# Main_ASCII.net
KiCad netlist of a schematic drawn in Altium Designer
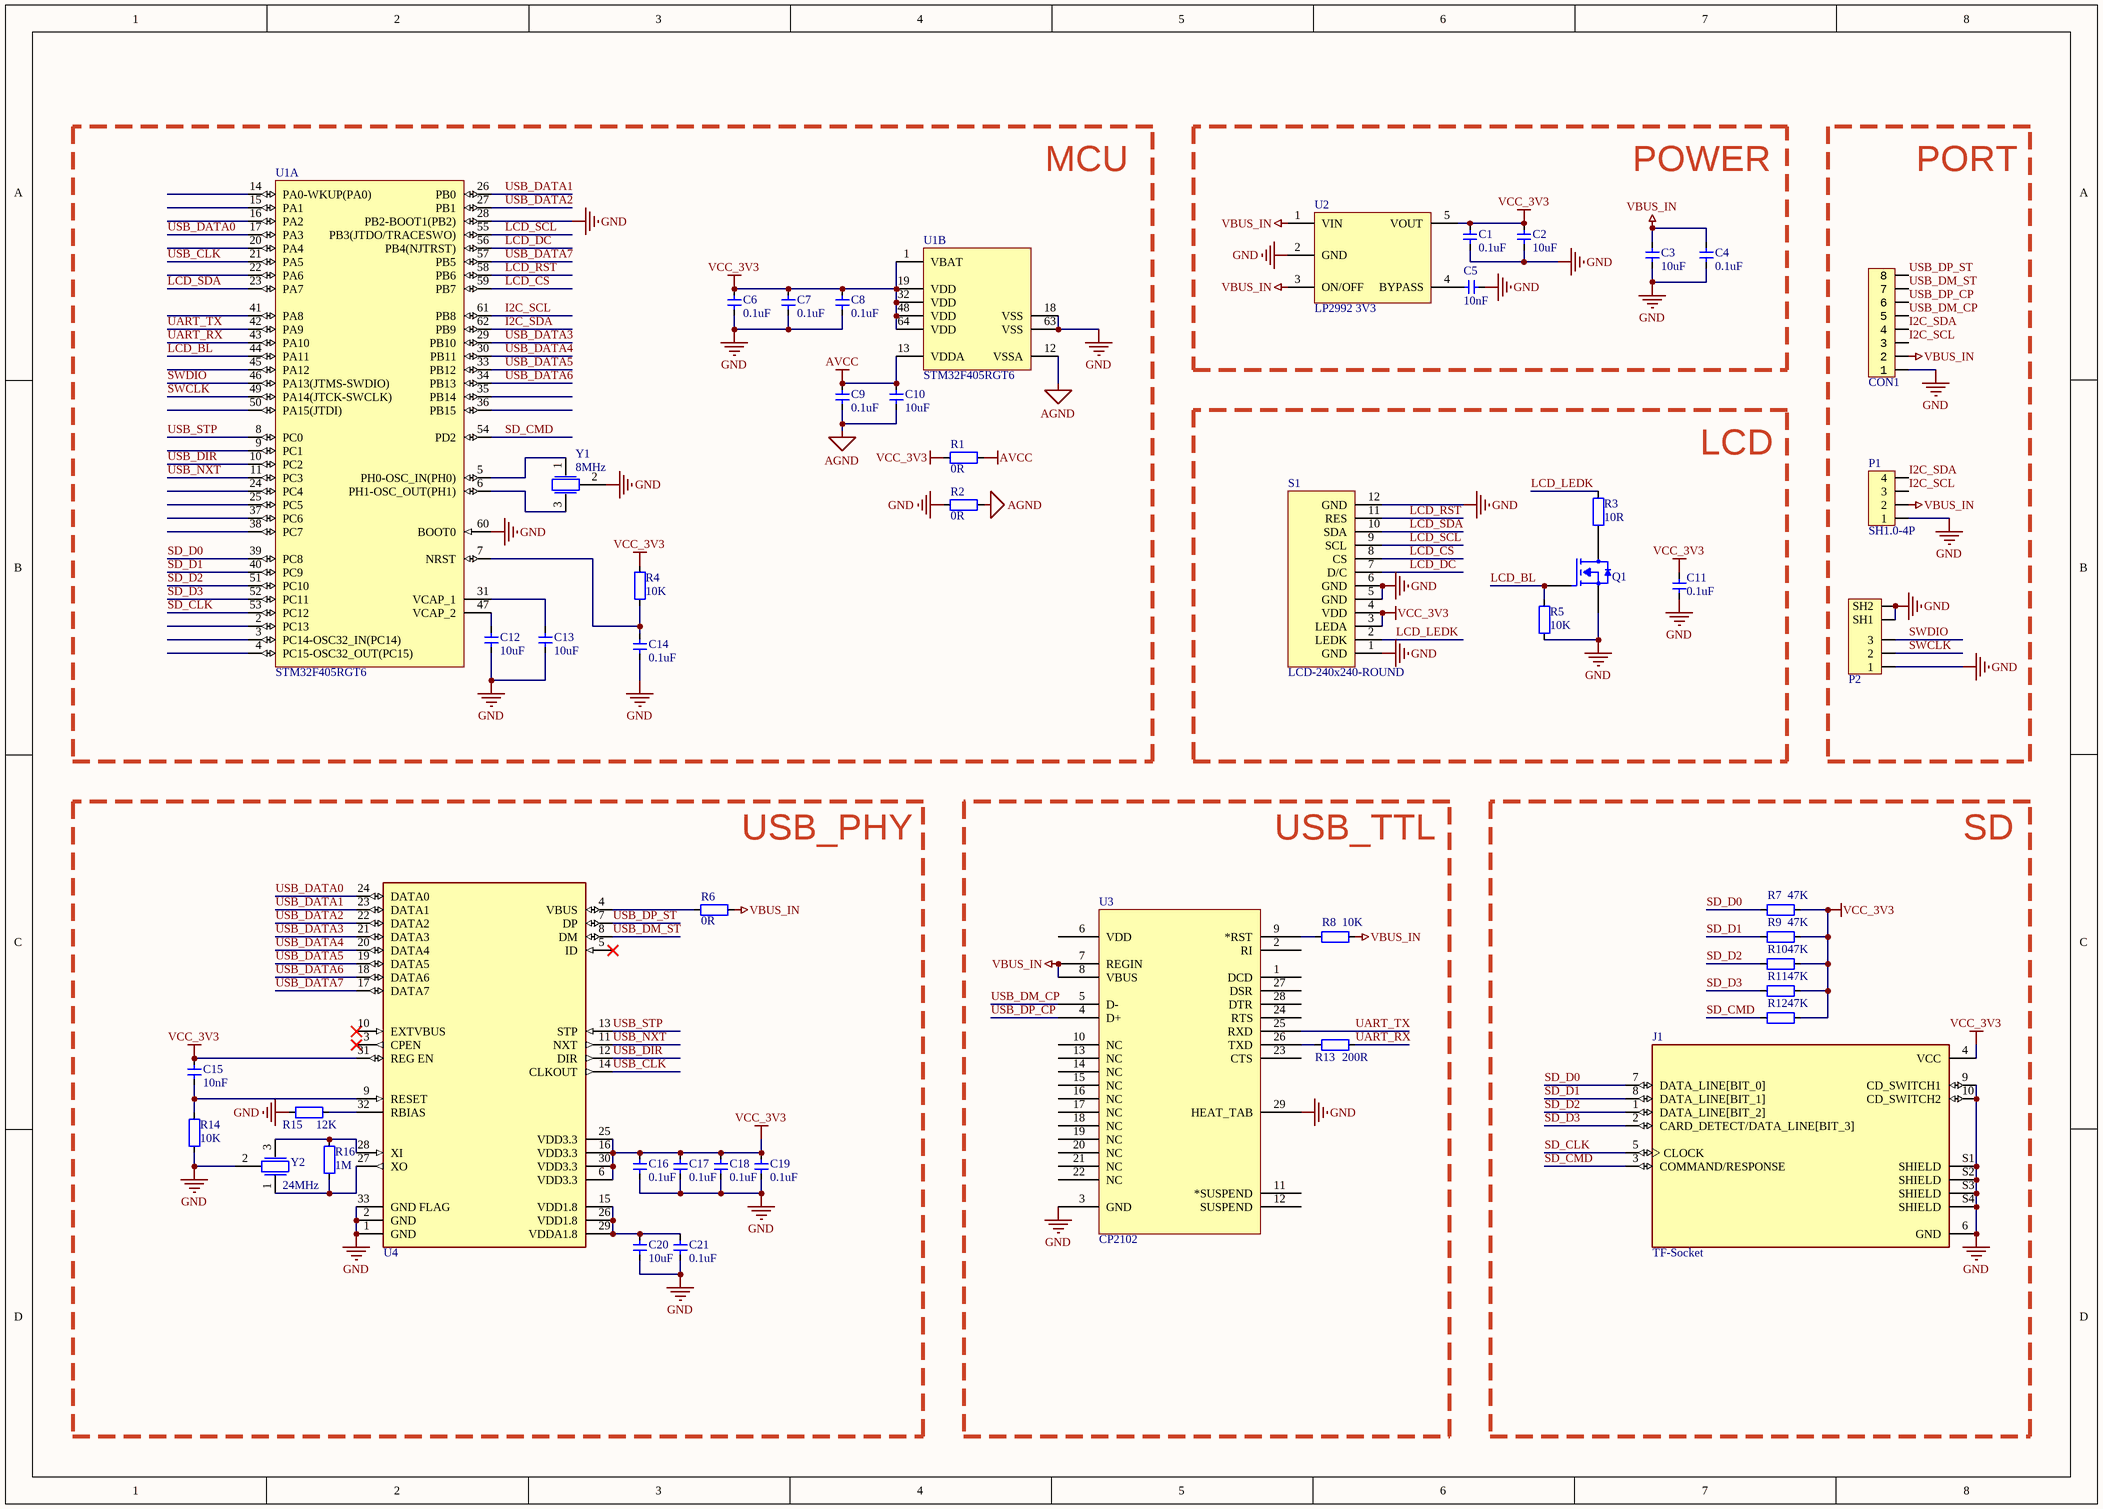
[diagram p0: Main_ASCII.SchDoc]

(export (version "E")
  (design (tool "Eeschema 10.0.6"))
  (components
    (comp (ref "C1")
      (value "0.1uF")
      (footprint "CAP_0402")
      (description "Capacitor")
      (libsource (lib "MyPcbLib") (part "电容-0402"))
    )
    (comp (ref "C2")
      (value "10uF")
      (footprint "CAP_0402")
      (description "Capacitor")
      (libsource (lib "MyPcbLib") (part "电容-0402"))
    )
    (comp (ref "C3")
      (value "10uF")
      (footprint "CAP_0402")
      (description "Capacitor")
      (libsource (lib "MyPcbLib") (part "电容-0402"))
    )
    (comp (ref "C4")
      (value "0.1uF")
      (footprint "CAP_0402")
      (description "Capacitor")
      (libsource (lib "MyPcbLib") (part "电容-0402"))
    )
    (comp (ref "C5")
      (value "10nF")
      (footprint "CAP_0402")
      (description "Capacitor")
      (libsource (lib "MyPcbLib") (part "电容-0402"))
    )
    (comp (ref "C6")
      (value "0.1uF")
      (footprint "CAP_0402")
      (description "Capacitor")
      (libsource (lib "MyPcbLib") (part "电容-0402"))
    )
    (comp (ref "C7")
      (value "0.1uF")
      (footprint "CAP_0402")
      (description "Capacitor")
      (libsource (lib "MyPcbLib") (part "电容-0402"))
    )
    (comp (ref "C8")
      (value "0.1uF")
      (footprint "CAP_0402")
      (description "Capacitor")
      (libsource (lib "MyPcbLib") (part "电容-0402"))
    )
    (comp (ref "C9")
      (value "0.1uF")
      (footprint "CAP_0402")
      (description "Capacitor")
      (libsource (lib "MyPcbLib") (part "电容-0402"))
    )
    (comp (ref "C10")
      (value "10uF")
      (footprint "CAP_0402")
      (description "Capacitor")
      (libsource (lib "MyPcbLib") (part "电容-0402"))
    )
    (comp (ref "C11")
      (value "0.1uF")
      (footprint "CAP_0402")
      (description "Capacitor")
      (libsource (lib "MyPcbLib") (part "电容-0402"))
    )
    (comp (ref "C12")
      (value "10uF")
      (footprint "CAP_0402")
      (description "Capacitor")
      (libsource (lib "MyPcbLib") (part "电容-0402"))
    )
    (comp (ref "C13")
      (value "10uF")
      (footprint "CAP_0402")
      (description "Capacitor")
      (libsource (lib "MyPcbLib") (part "电容-0402"))
    )
    (comp (ref "C14")
      (value "0.1uF")
      (footprint "CAP_0402")
      (description "Capacitor")
      (libsource (lib "MyPcbLib") (part "电容-0402"))
    )
    (comp (ref "C15")
      (value "10nF")
      (footprint "CAP_0402")
      (description "Capacitor")
      (libsource (lib "MyPcbLib") (part "电容-0402"))
    )
    (comp (ref "C16")
      (value "0.1uF")
      (footprint "CAP_0402")
      (description "Capacitor")
      (libsource (lib "MyPcbLib") (part "电容-0402"))
    )
    (comp (ref "C17")
      (value "0.1uF")
      (footprint "CAP_0402")
      (description "Capacitor")
      (libsource (lib "MyPcbLib") (part "电容-0402"))
    )
    (comp (ref "C18")
      (value "0.1uF")
      (footprint "CAP_0402")
      (description "Capacitor")
      (libsource (lib "MyPcbLib") (part "电容-0402"))
    )
    (comp (ref "C19")
      (value "0.1uF")
      (footprint "CAP_0402")
      (description "Capacitor")
      (libsource (lib "MyPcbLib") (part "电容-0402"))
    )
    (comp (ref "C20")
      (value "10uF")
      (footprint "CAP_0402")
      (description "Capacitor")
      (libsource (lib "MyPcbLib") (part "电容-0402"))
    )
    (comp (ref "C21")
      (value "0.1uF")
      (footprint "CAP_0402")
      (description "Capacitor")
      (libsource (lib "MyPcbLib") (part "电容-0402"))
    )
    (comp (ref "CON1")
      (value "FFC_0.5_8")
      (footprint "FFC_0.5_8")
      (description "FFC")
      (libsource (lib "KitSprout") (part "FFC_0.5_8"))
    )
    (comp (ref "J1")
      (value "TF-Socket")
      (footprint "TF-Card-Amphenol with TF")
      (description "10 _8 + 2_ Position Card Connector Secure Digital - microSDâ„¢ Surface Mount, Right Angle Gold")
      (fields (field (name "MP") "1140084168") (field (name "MF") "Amphenol Commercial Products"))
      (libsource (lib "MyPcbLib") (part "TF-Socket"))
    )
    (comp (ref "P1") (value "SH1.0-4P") (footprint "SH1.0-4P") (libsource (lib "MyPcbLib") (part "SH1.0-4P")))
    (comp (ref "P2")
      (value "SH1.0-3P-STAND")
      (footprint "SH1.0-3P-STAND")
      (description "Header")
      (libsource (lib "MyPcbLib") (part "SH1.0-3P-STAND"))
    )
    (comp (ref "Q1")
      (value "AO3400A")
      (footprint "SOT23-3")
      (description "N-MOS")
      (libsource (lib "MyPcbLib") (part "AO3400A"))
    )
    (comp (ref "R1")
      (value "0R")
      (footprint "RES_0402")
      (description "Resistor")
      (libsource (lib "") (part "电阻-0402_1"))
    )
    (comp (ref "R2")
      (value "0R")
      (footprint "RES_0402")
      (description "Resistor")
      (libsource (lib "") (part "电阻-0402_1"))
    )
    (comp (ref "R3")
      (value "10R")
      (footprint "RES_0402")
      (description "Resistor")
      (libsource (lib "") (part "电阻-0402_2"))
    )
    (comp (ref "R4")
      (value "10K")
      (footprint "RES_0402")
      (description "Resistor")
      (libsource (lib "") (part "电阻-0402_2"))
    )
    (comp (ref "R5")
      (value "10K")
      (footprint "RES_0402")
      (description "Resistor")
      (libsource (lib "") (part "电阻-0402_2"))
    )
    (comp (ref "R6")
      (value "0R")
      (footprint "RES_0402")
      (description "Resistor")
      (libsource (lib "") (part "电阻-0402_1"))
    )
    (comp (ref "R7")
      (value "47K")
      (footprint "RES_0402")
      (description "Resistor")
      (libsource (lib "") (part "电阻-0402_1"))
    )
    (comp (ref "R8")
      (value "10K")
      (footprint "RES_0402")
      (description "Resistor")
      (libsource (lib "") (part "电阻-0402_1"))
    )
    (comp (ref "R9")
      (value "47K")
      (footprint "RES_0402")
      (description "Resistor")
      (libsource (lib "") (part "电阻-0402_1"))
    )
    (comp (ref "R10")
      (value "47K")
      (footprint "RES_0402")
      (description "Resistor")
      (libsource (lib "") (part "电阻-0402_1"))
    )
    (comp (ref "R11")
      (value "47K")
      (footprint "RES_0402")
      (description "Resistor")
      (libsource (lib "") (part "电阻-0402_1"))
    )
    (comp (ref "R12")
      (value "47K")
      (footprint "RES_0402")
      (description "Resistor")
      (libsource (lib "") (part "电阻-0402_1"))
    )
    (comp (ref "R13")
      (value "200R")
      (footprint "RES_0402")
      (description "Resistor")
      (libsource (lib "") (part "电阻-0402_1"))
    )
    (comp (ref "R14")
      (value "10K")
      (footprint "RES_0402")
      (description "Resistor")
      (libsource (lib "MyPcbLib") (part "电阻-0402"))
    )
    (comp (ref "R15")
      (value "12K")
      (footprint "RES_0402")
      (description "Resistor")
      (libsource (lib "") (part "电阻-0402_1"))
    )
    (comp (ref "R16")
      (value "1M")
      (footprint "RES_0402")
      (description "Resistor")
      (libsource (lib "MyPcbLib") (part "电阻-0402"))
    )
    (comp (ref "S1")
      (value "LCD-240x240-ROUND")
      (footprint "LCD-240x240-ROUND")
      (description "显示屏")
      (libsource (lib "mLib") (part "LCD-240x240-ROUND"))
    )
    (comp (ref "U1")
      (value "STM32F405RGT6")
      (footprint "LQFP-64_N")
      (fields (field (name "MANUFACTURER") "STMicroelectronics"))
      (libsource (lib "STMicroelectronics STM32 F4") (part "STM32F405RGT6"))
    )
    (comp (ref "U2")
      (value "LP2992 3V3")
      (footprint "SOT23-5")
      (description "LDO")
      (libsource (lib "MyPcbLib") (part "LP2992"))
    )
    (comp (ref "U3")
      (value "CP2102")
      (footprint "QFN-28")
      (description "USB转TTL")
      (libsource (lib "mLib") (part "CP2102"))
    )
    (comp (ref "U4")
      (value "USB3300-EZK-TR")
      (footprint "QFN-32")
      (libsource (lib "mLib") (part "USB3300-EZK-TR"))
    )
    (comp (ref "Y1")
      (value "8MHz")
      (footprint "晶振-3P")
      (description "村田贴片")
      (libsource (lib "MyPcbLib") (part "晶振-3Pin"))
    )
    (comp (ref "Y2")
      (value "24MHz")
      (footprint "晶振-3P")
      (description "村田贴片")
      (libsource (lib "MyPcbLib") (part "晶振-3Pin"))
    )
  )
  (nets
    (net (code "1") (name "/I2C_SCL") (class "Default")
      (node (ref "CON1") (pin "3") (pinfunction "3_3") (pintype "passive"))
      (node (ref "P1") (pin "3") (pinfunction "3_3") (pintype "passive"))
      (node (ref "U1") (pin "61") (pinfunction "PB8_61") (pintype "bidirectional"))
    )
    (net (code "2") (name "/I2C_SDA") (class "Default")
      (node (ref "CON1") (pin "4") (pinfunction "4_4") (pintype "passive"))
      (node (ref "P1") (pin "4") (pinfunction "4_4") (pintype "passive"))
      (node (ref "U1") (pin "62") (pinfunction "PB9_62") (pintype "bidirectional"))
    )
    (net (code "3") (name "/LCD_BL") (class "Default")
      (node (ref "Q1") (pin "1") (pinfunction "G_1") (pintype "passive"))
      (node (ref "R5") (pin "2") (pinfunction "2_2") (pintype "passive"))
      (node (ref "U1") (pin "44") (pinfunction "PA11_44") (pintype "bidirectional"))
    )
    (net (code "4") (name "/LCD_CS") (class "Default")
      (node (ref "S1") (pin "8") (pinfunction "CS_8") (pintype "passive"))
      (node (ref "U1") (pin "59") (pinfunction "PB7_59") (pintype "bidirectional"))
    )
    (net (code "5") (name "/LCD_DC") (class "Default")
      (node (ref "S1") (pin "7") (pinfunction "D/C_7") (pintype "passive"))
      (node (ref "U1") (pin "56") (pinfunction "PB4(NJTRST)_56") (pintype "bidirectional"))
    )
    (net (code "6") (name "/LCD_LEDK") (class "Default")
      (node (ref "R3") (pin "2") (pinfunction "2_2") (pintype "passive"))
      (node (ref "S1") (pin "2") (pinfunction "LEDK_2") (pintype "passive"))
    )
    (net (code "7") (name "/LCD_RST") (class "Default")
      (node (ref "S1") (pin "11") (pinfunction "RES_11") (pintype "passive"))
      (node (ref "U1") (pin "58") (pinfunction "PB6_58") (pintype "bidirectional"))
    )
    (net (code "8") (name "/LCD_SCL") (class "Default")
      (node (ref "S1") (pin "9") (pinfunction "SCL_9") (pintype "passive"))
      (node (ref "U1") (pin "55") (pinfunction "PB3(JTDO/TRACESWO)_55") (pintype "bidirectional"))
    )
    (net (code "9") (name "/LCD_SDA") (class "Default")
      (node (ref "S1") (pin "10") (pinfunction "SDA_10") (pintype "passive"))
      (node (ref "U1") (pin "23") (pinfunction "PA7_23") (pintype "bidirectional"))
    )
    (net (code "10") (name "/SD_CLK") (class "Default")
      (node (ref "J1") (pin "5") (pinfunction "CLOCK_5") (pintype "bidirectional"))
      (node (ref "U1") (pin "53") (pinfunction "PC12_53") (pintype "bidirectional"))
    )
    (net (code "11") (name "/SD_CMD") (class "Default")
      (node (ref "J1") (pin "3") (pinfunction "COMMAND/RESPONSE_3") (pintype "bidirectional"))
      (node (ref "R12") (pin "2") (pinfunction "2_2") (pintype "passive"))
      (node (ref "U1") (pin "54") (pinfunction "PD2_54") (pintype "bidirectional"))
    )
    (net (code "12") (name "/SD_D0") (class "Default")
      (node (ref "J1") (pin "7") (pinfunction "DATA_LINE[BIT_0]_7") (pintype "bidirectional"))
      (node (ref "R7") (pin "2") (pinfunction "2_2") (pintype "passive"))
      (node (ref "U1") (pin "39") (pinfunction "PC8_39") (pintype "bidirectional"))
    )
    (net (code "13") (name "/SD_D1") (class "Default")
      (node (ref "J1") (pin "8") (pinfunction "DATA_LINE[BIT_1]_8") (pintype "bidirectional"))
      (node (ref "R9") (pin "2") (pinfunction "2_2") (pintype "passive"))
      (node (ref "U1") (pin "40") (pinfunction "PC9_40") (pintype "bidirectional"))
    )
    (net (code "14") (name "/SD_D2") (class "Default")
      (node (ref "J1") (pin "1") (pinfunction "DATA_LINE[BIT_2]_1") (pintype "bidirectional"))
      (node (ref "R10") (pin "2") (pinfunction "2_2") (pintype "passive"))
      (node (ref "U1") (pin "51") (pinfunction "PC10_51") (pintype "bidirectional"))
    )
    (net (code "15") (name "/SD_D3") (class "Default")
      (node (ref "J1") (pin "2") (pinfunction "CARD_DETECT/DATA_LINE[BIT_3]_2") (pintype "bidirectional"))
      (node (ref "R11") (pin "2") (pinfunction "2_2") (pintype "passive"))
      (node (ref "U1") (pin "52") (pinfunction "PC11_52") (pintype "bidirectional"))
    )
    (net (code "16") (name "/SWCLK") (class "Default")
      (node (ref "P2") (pin "2") (pinfunction "2_2") (pintype "passive"))
      (node (ref "U1") (pin "49") (pinfunction "PA14(JTCK-SWCLK)_49") (pintype "bidirectional"))
    )
    (net (code "17") (name "/SWDIO") (class "Default")
      (node (ref "P2") (pin "3") (pinfunction "3_3") (pintype "passive"))
      (node (ref "U1") (pin "46") (pinfunction "PA13(JTMS-SWDIO)_46") (pintype "bidirectional"))
    )
    (net (code "18") (name "/UART_RX") (class "Default")
      (node (ref "R13") (pin "1") (pinfunction "1_1") (pintype "passive"))
      (node (ref "U1") (pin "43") (pinfunction "PA10_43") (pintype "bidirectional"))
    )
    (net (code "19") (name "/UART_TX") (class "Default")
      (node (ref "U1") (pin "42") (pinfunction "PA9_42") (pintype "bidirectional"))
      (node (ref "U3") (pin "25") (pinfunction "RXD_25") (pintype "passive"))
    )
    (net (code "20") (name "/USB_CLK") (class "Default")
      (node (ref "U1") (pin "21") (pinfunction "PA5_21") (pintype "bidirectional"))
      (node (ref "U4") (pin "14") (pinfunction "CLKOUT_14") (pintype "output"))
    )
    (net (code "21") (name "/USB_DATA0") (class "Default")
      (node (ref "U1") (pin "17") (pinfunction "PA3_17") (pintype "bidirectional"))
      (node (ref "U4") (pin "24") (pinfunction "DATA0_24") (pintype "bidirectional"))
    )
    (net (code "22") (name "/USB_DATA1") (class "Default")
      (node (ref "U1") (pin "26") (pinfunction "PB0_26") (pintype "bidirectional"))
      (node (ref "U4") (pin "23") (pinfunction "DATA1_23") (pintype "bidirectional"))
    )
    (net (code "23") (name "/USB_DATA2") (class "Default")
      (node (ref "U1") (pin "27") (pinfunction "PB1_27") (pintype "bidirectional"))
      (node (ref "U4") (pin "22") (pinfunction "DATA2_22") (pintype "bidirectional"))
    )
    (net (code "24") (name "/USB_DATA3") (class "Default")
      (node (ref "U1") (pin "29") (pinfunction "PB10_29") (pintype "bidirectional"))
      (node (ref "U4") (pin "21") (pinfunction "DATA3_21") (pintype "bidirectional"))
    )
    (net (code "25") (name "/USB_DATA4") (class "Default")
      (node (ref "U1") (pin "30") (pinfunction "PB11_30") (pintype "bidirectional"))
      (node (ref "U4") (pin "20") (pinfunction "DATA4_20") (pintype "bidirectional"))
    )
    (net (code "26") (name "/USB_DATA5") (class "Default")
      (node (ref "U1") (pin "33") (pinfunction "PB12_33") (pintype "bidirectional"))
      (node (ref "U4") (pin "19") (pinfunction "DATA5_19") (pintype "bidirectional"))
    )
    (net (code "27") (name "/USB_DATA6") (class "Default")
      (node (ref "U1") (pin "34") (pinfunction "PB13_34") (pintype "bidirectional"))
      (node (ref "U4") (pin "18") (pinfunction "DATA6_18") (pintype "bidirectional"))
    )
    (net (code "28") (name "/USB_DATA7") (class "Default")
      (node (ref "U1") (pin "57") (pinfunction "PB5_57") (pintype "bidirectional"))
      (node (ref "U4") (pin "17") (pinfunction "DATA7_17") (pintype "bidirectional"))
    )
    (net (code "29") (name "/USB_DIR") (class "Default")
      (node (ref "U1") (pin "10") (pinfunction "PC2_10") (pintype "bidirectional"))
      (node (ref "U4") (pin "12") (pinfunction "DIR_12") (pintype "output"))
    )
    (net (code "30") (name "/USB_DM_CP") (class "Default")
      (node (ref "CON1") (pin "5") (pinfunction "5_5") (pintype "passive"))
      (node (ref "U3") (pin "5") (pinfunction "D-_5") (pintype "passive"))
    )
    (net (code "31") (name "/USB_DM_ST") (class "Default")
      (node (ref "CON1") (pin "7") (pinfunction "7_7") (pintype "passive"))
      (node (ref "U4") (pin "8") (pinfunction "DM_8") (pintype "bidirectional"))
    )
    (net (code "32") (name "/USB_DP_CP") (class "Default")
      (node (ref "CON1") (pin "6") (pinfunction "6_6") (pintype "passive"))
      (node (ref "U3") (pin "4") (pinfunction "D+_4") (pintype "passive"))
    )
    (net (code "33") (name "/USB_DP_ST") (class "Default")
      (node (ref "CON1") (pin "8") (pinfunction "8_8") (pintype "passive"))
      (node (ref "U4") (pin "7") (pinfunction "DP_7") (pintype "bidirectional"))
    )
    (net (code "34") (name "/USB_NXT") (class "Default")
      (node (ref "U1") (pin "11") (pinfunction "PC3_11") (pintype "bidirectional"))
      (node (ref "U4") (pin "11") (pinfunction "NXT_11") (pintype "output"))
    )
    (net (code "35") (name "/USB_STP") (class "Default")
      (node (ref "U1") (pin "8") (pinfunction "PC0_8") (pintype "bidirectional"))
      (node (ref "U4") (pin "13") (pinfunction "STP_13") (pintype "input"))
    )
    (net (code "36") (name "AGND") (class "Default")
      (node (ref "C10") (pin "1") (pinfunction "1_1") (pintype "passive"))
      (node (ref "C9") (pin "1") (pinfunction "1_1") (pintype "passive"))
      (node (ref "R2") (pin "1") (pinfunction "1_1") (pintype "passive"))
      (node (ref "U1") (pin "12") (pinfunction "VSSA_12") (pintype "power_in"))
    )
    (net (code "37") (name "AVCC") (class "Default")
      (node (ref "C10") (pin "2") (pinfunction "2_2") (pintype "passive"))
      (node (ref "C9") (pin "2") (pinfunction "2_2") (pintype "passive"))
      (node (ref "R1") (pin "1") (pinfunction "1_1") (pintype "passive"))
      (node (ref "U1") (pin "13") (pinfunction "VDDA_13") (pintype "power_in"))
    )
    (net (code "38") (name "GND") (class "Default")
      (node (ref "C1") (pin "1") (pinfunction "1_1") (pintype "passive"))
      (node (ref "C11") (pin "1") (pinfunction "1_1") (pintype "passive"))
      (node (ref "C12") (pin "1") (pinfunction "1_1") (pintype "passive"))
      (node (ref "C13") (pin "1") (pinfunction "1_1") (pintype "passive"))
      (node (ref "C14") (pin "1") (pinfunction "1_1") (pintype "passive"))
      (node (ref "C16") (pin "2") (pinfunction "2_2") (pintype "passive"))
      (node (ref "C17") (pin "2") (pinfunction "2_2") (pintype "passive"))
      (node (ref "C18") (pin "2") (pinfunction "2_2") (pintype "passive"))
      (node (ref "C19") (pin "2") (pinfunction "2_2") (pintype "passive"))
      (node (ref "C2") (pin "1") (pinfunction "1_1") (pintype "passive"))
      (node (ref "C20") (pin "2") (pinfunction "2_2") (pintype "passive"))
      (node (ref "C21") (pin "2") (pinfunction "2_2") (pintype "passive"))
      (node (ref "C3") (pin "1") (pinfunction "1_1") (pintype "passive"))
      (node (ref "C4") (pin "1") (pinfunction "1_1") (pintype "passive"))
      (node (ref "C5") (pin "1") (pinfunction "1_1") (pintype "passive"))
      (node (ref "C6") (pin "1") (pinfunction "1_1") (pintype "passive"))
      (node (ref "C7") (pin "1") (pinfunction "1_1") (pintype "passive"))
      (node (ref "C8") (pin "1") (pinfunction "1_1") (pintype "passive"))
      (node (ref "CON1") (pin "1") (pinfunction "1_1") (pintype "passive"))
      (node (ref "J1") (pin "10") (pinfunction "CD_SWITCH2_10") (pintype "bidirectional"))
      (node (ref "J1") (pin "6") (pinfunction "GND_6") (pintype "power_in"))
      (node (ref "J1") (pin "9") (pinfunction "CD_SWITCH1_9") (pintype "bidirectional"))
      (node (ref "J1") (pin "S1") (pinfunction "SHIELD_S1") (pintype "passive"))
      (node (ref "J1") (pin "S2") (pinfunction "SHIELD_S2") (pintype "passive"))
      (node (ref "J1") (pin "S3") (pinfunction "SHIELD_S3") (pintype "passive"))
      (node (ref "J1") (pin "S4") (pinfunction "SHIELD_S4") (pintype "passive"))
      (node (ref "P1") (pin "1") (pinfunction "1_1") (pintype "passive"))
      (node (ref "P2") (pin "1") (pinfunction "1_1") (pintype "passive"))
      (node (ref "P2") (pin "SH1") (pinfunction "SH1_SH1") (pintype "passive"))
      (node (ref "P2") (pin "SH2") (pinfunction "SH2_SH2") (pintype "passive"))
      (node (ref "Q1") (pin "2") (pinfunction "S_2") (pintype "passive"))
      (node (ref "R14") (pin "2") (pinfunction "2_2") (pintype "passive"))
      (node (ref "R15") (pin "2") (pinfunction "2_2") (pintype "passive"))
      (node (ref "R2") (pin "2") (pinfunction "2_2") (pintype "passive"))
      (node (ref "R5") (pin "1") (pinfunction "1_1") (pintype "passive"))
      (node (ref "S1") (pin "1") (pinfunction "GND_1") (pintype "passive"))
      (node (ref "S1") (pin "12") (pinfunction "GND_12") (pintype "passive"))
      (node (ref "S1") (pin "5") (pinfunction "GND_5") (pintype "passive"))
      (node (ref "S1") (pin "6") (pinfunction "GND_6") (pintype "passive"))
      (node (ref "U1") (pin "18") (pinfunction "VSS_18") (pintype "power_in"))
      (node (ref "U1") (pin "28") (pinfunction "PB2-BOOT1(PB2)_28") (pintype "bidirectional"))
      (node (ref "U1") (pin "60") (pinfunction "BOOT0_60") (pintype "input"))
      (node (ref "U1") (pin "63") (pinfunction "VSS_63") (pintype "power_in"))
      (node (ref "U2") (pin "2") (pinfunction "GND_2") (pintype "passive"))
      (node (ref "U3") (pin "29") (pinfunction "HEAT_TAB_29") (pintype "passive"))
      (node (ref "U3") (pin "3") (pinfunction "GND_3") (pintype "passive"))
      (node (ref "U4") (pin "1") (pinfunction "GND_1") (pintype "power_in"))
      (node (ref "U4") (pin "2") (pinfunction "GND_2") (pintype "power_in"))
      (node (ref "U4") (pin "33") (pinfunction "GND_FLAG_33") (pintype "power_in"))
      (node (ref "Y1") (pin "2") (pinfunction "2_2") (pintype "passive"))
      (node (ref "Y2") (pin "2") (pinfunction "2_2") (pintype "passive"))
    )
    (net (code "39") (name "Net-(Q1-D)") (class "Default")
      (node (ref "Q1") (pin "3") (pinfunction "D_3") (pintype "passive"))
      (node (ref "R3") (pin "1") (pinfunction "1_1") (pintype "passive"))
    )
    (net (code "40") (name "Net-(U1A-NRST)") (class "Default")
      (node (ref "C14") (pin "2") (pinfunction "2_2") (pintype "passive"))
      (node (ref "R4") (pin "1") (pinfunction "1_1") (pintype "passive"))
      (node (ref "U1") (pin "7") (pinfunction "NRST_7") (pintype "bidirectional"))
    )
    (net (code "41") (name "Net-(U1A-PH0-OSC_IN(PH0))") (class "Default")
      (node (ref "U1") (pin "5") (pinfunction "PH0-OSC_IN(PH0)_5") (pintype "bidirectional"))
      (node (ref "Y1") (pin "1") (pinfunction "1_1") (pintype "passive"))
    )
    (net (code "42") (name "Net-(U1A-PH1-OSC_OUT(PH1))") (class "Default")
      (node (ref "U1") (pin "6") (pinfunction "PH1-OSC_OUT(PH1)_6") (pintype "bidirectional"))
      (node (ref "Y1") (pin "3") (pinfunction "3_3") (pintype "passive"))
    )
    (net (code "43") (name "Net-(U1A-VCAP_1)") (class "Default")
      (node (ref "C13") (pin "2") (pinfunction "2_2") (pintype "passive"))
      (node (ref "U1") (pin "31") (pinfunction "VCAP_1_31") (pintype "power_in"))
    )
    (net (code "44") (name "Net-(U1A-VCAP_2)") (class "Default")
      (node (ref "C12") (pin "2") (pinfunction "2_2") (pintype "passive"))
      (node (ref "U1") (pin "47") (pinfunction "VCAP_2_47") (pintype "power_in"))
    )
    (net (code "45") (name "Net-(U2-BYPASS)") (class "Default")
      (node (ref "C5") (pin "2") (pinfunction "2_2") (pintype "passive"))
      (node (ref "U2") (pin "4") (pinfunction "BYPASS_4") (pintype "passive"))
    )
    (net (code "46") (name "Net-(U3-*RST)") (class "Default")
      (node (ref "R8") (pin "2") (pinfunction "2_2") (pintype "passive"))
      (node (ref "U3") (pin "9") (pinfunction "*RST_9") (pintype "passive"))
    )
    (net (code "47") (name "Net-(U3-TXD)") (class "Default")
      (node (ref "R13") (pin "2") (pinfunction "2_2") (pintype "passive"))
      (node (ref "U3") (pin "26") (pinfunction "TXD_26") (pintype "passive"))
    )
    (net (code "48") (name "Net-(U4-RBIAS)") (class "Default")
      (node (ref "R15") (pin "1") (pinfunction "1_1") (pintype "passive"))
      (node (ref "U4") (pin "32") (pinfunction "RBIAS_32") (pintype "power_in"))
    )
    (net (code "49") (name "Net-(U4-RESET)") (class "Default")
      (node (ref "C15") (pin "2") (pinfunction "2_2") (pintype "passive"))
      (node (ref "R14") (pin "1") (pinfunction "1_1") (pintype "passive"))
      (node (ref "U4") (pin "9") (pinfunction "RESET_9") (pintype "input"))
    )
    (net (code "50") (name "Net-(U4-VBUS)") (class "Default")
      (node (ref "R6") (pin "2") (pinfunction "2_2") (pintype "passive"))
      (node (ref "U4") (pin "4") (pinfunction "VBUS_4") (pintype "bidirectional"))
    )
    (net (code "51") (name "Net-(U4-VDDA1.8)") (class "Default")
      (node (ref "C20") (pin "1") (pinfunction "1_1") (pintype "passive"))
      (node (ref "C21") (pin "1") (pinfunction "1_1") (pintype "passive"))
      (node (ref "U4") (pin "15") (pinfunction "VDD1.8_15") (pintype "power_in"))
      (node (ref "U4") (pin "26") (pinfunction "VDD1.8_26") (pintype "power_in"))
      (node (ref "U4") (pin "29") (pinfunction "VDDA1.8_29") (pintype "power_in"))
    )
    (net (code "52") (name "Net-(U4-XI)") (class "Default")
      (node (ref "R16") (pin "1") (pinfunction "1_1") (pintype "passive"))
      (node (ref "U4") (pin "28") (pinfunction "XI_28") (pintype "input"))
      (node (ref "Y2") (pin "3") (pinfunction "3_3") (pintype "passive"))
    )
    (net (code "53") (name "Net-(U4-XO)") (class "Default")
      (node (ref "R16") (pin "2") (pinfunction "2_2") (pintype "passive"))
      (node (ref "U4") (pin "27") (pinfunction "XO_27") (pintype "output"))
      (node (ref "Y2") (pin "1") (pinfunction "1_1") (pintype "passive"))
    )
    (net (code "54") (name "VBUS_IN") (class "Default")
      (node (ref "C3") (pin "2") (pinfunction "2_2") (pintype "passive"))
      (node (ref "C4") (pin "2") (pinfunction "2_2") (pintype "passive"))
      (node (ref "CON1") (pin "2") (pinfunction "2_2") (pintype "passive"))
      (node (ref "P1") (pin "2") (pinfunction "2_2") (pintype "passive"))
      (node (ref "R6") (pin "1") (pinfunction "1_1") (pintype "passive"))
      (node (ref "R8") (pin "1") (pinfunction "1_1") (pintype "passive"))
      (node (ref "U2") (pin "1") (pinfunction "VIN_1") (pintype "passive"))
      (node (ref "U2") (pin "3") (pinfunction "ON/OFF_3") (pintype "passive"))
      (node (ref "U3") (pin "7") (pinfunction "REGIN_7") (pintype "passive"))
      (node (ref "U3") (pin "8") (pinfunction "VBUS_8") (pintype "passive"))
    )
    (net (code "55") (name "VCC_3V3") (class "Default")
      (node (ref "C1") (pin "2") (pinfunction "2_2") (pintype "passive"))
      (node (ref "C11") (pin "2") (pinfunction "2_2") (pintype "passive"))
      (node (ref "C15") (pin "1") (pinfunction "1_1") (pintype "passive"))
      (node (ref "C16") (pin "1") (pinfunction "1_1") (pintype "passive"))
      (node (ref "C17") (pin "1") (pinfunction "1_1") (pintype "passive"))
      (node (ref "C18") (pin "1") (pinfunction "1_1") (pintype "passive"))
      (node (ref "C19") (pin "1") (pinfunction "1_1") (pintype "passive"))
      (node (ref "C2") (pin "2") (pinfunction "2_2") (pintype "passive"))
      (node (ref "C6") (pin "2") (pinfunction "2_2") (pintype "passive"))
      (node (ref "C7") (pin "2") (pinfunction "2_2") (pintype "passive"))
      (node (ref "C8") (pin "2") (pinfunction "2_2") (pintype "passive"))
      (node (ref "J1") (pin "4") (pinfunction "VCC_4") (pintype "power_in"))
      (node (ref "R1") (pin "2") (pinfunction "2_2") (pintype "passive"))
      (node (ref "R10") (pin "1") (pinfunction "1_1") (pintype "passive"))
      (node (ref "R11") (pin "1") (pinfunction "1_1") (pintype "passive"))
      (node (ref "R12") (pin "1") (pinfunction "1_1") (pintype "passive"))
      (node (ref "R4") (pin "2") (pinfunction "2_2") (pintype "passive"))
      (node (ref "R7") (pin "1") (pinfunction "1_1") (pintype "passive"))
      (node (ref "R9") (pin "1") (pinfunction "1_1") (pintype "passive"))
      (node (ref "S1") (pin "3") (pinfunction "LEDA_3") (pintype "passive"))
      (node (ref "S1") (pin "4") (pinfunction "VDD_4") (pintype "passive"))
      (node (ref "U1") (pin "1") (pinfunction "VBAT_1") (pintype "power_in"))
      (node (ref "U1") (pin "19") (pinfunction "VDD_19") (pintype "power_in"))
      (node (ref "U1") (pin "32") (pinfunction "VDD_32") (pintype "power_in"))
      (node (ref "U1") (pin "48") (pinfunction "VDD_48") (pintype "power_in"))
      (node (ref "U1") (pin "64") (pinfunction "VDD_64") (pintype "power_in"))
      (node (ref "U2") (pin "5") (pinfunction "VOUT_5") (pintype "passive"))
      (node (ref "U4") (pin "16") (pinfunction "VDD3.3_16") (pintype "power_in"))
      (node (ref "U4") (pin "25") (pinfunction "VDD3.3_25") (pintype "power_in"))
      (node (ref "U4") (pin "30") (pinfunction "VDD3.3_30") (pintype "power_in"))
      (node (ref "U4") (pin "31") (pinfunction "REG_EN_31") (pintype "bidirectional"))
      (node (ref "U4") (pin "6") (pinfunction "VDD3.3_6") (pintype "power_in"))
    )
    (net (code "56") (name "unconnected-(U1A-PA0-WKUP(PA0)-Pad14)") (class "Default")
      (node (ref "U1") (pin "14") (pinfunction "PA0-WKUP(PA0)_14") (pintype "bidirectional"))
    )
    (net (code "57") (name "unconnected-(U1A-PA1-Pad15)") (class "Default")
      (node (ref "U1") (pin "15") (pinfunction "PA1_15") (pintype "bidirectional"))
    )
    (net (code "58") (name "unconnected-(U1A-PA2-Pad16)") (class "Default")
      (node (ref "U1") (pin "16") (pinfunction "PA2_16") (pintype "bidirectional"))
    )
    (net (code "59") (name "unconnected-(U1A-PA4-Pad20)") (class "Default")
      (node (ref "U1") (pin "20") (pinfunction "PA4_20") (pintype "bidirectional"))
    )
    (net (code "60") (name "unconnected-(U1A-PA6-Pad22)") (class "Default")
      (node (ref "U1") (pin "22") (pinfunction "PA6_22") (pintype "bidirectional"))
    )
    (net (code "61") (name "unconnected-(U1A-PA8-Pad41)") (class "Default")
      (node (ref "U1") (pin "41") (pinfunction "PA8_41") (pintype "bidirectional"))
    )
    (net (code "62") (name "unconnected-(U1A-PA12-Pad45)") (class "Default")
      (node (ref "U1") (pin "45") (pinfunction "PA12_45") (pintype "bidirectional"))
    )
    (net (code "63") (name "unconnected-(U1A-PA15(JTDI)-Pad50)") (class "Default")
      (node (ref "U1") (pin "50") (pinfunction "PA15(JTDI)_50") (pintype "bidirectional"))
    )
    (net (code "64") (name "unconnected-(U1A-PB14-Pad35)") (class "Default")
      (node (ref "U1") (pin "35") (pinfunction "PB14_35") (pintype "bidirectional"))
    )
    (net (code "65") (name "unconnected-(U1A-PB15-Pad36)") (class "Default")
      (node (ref "U1") (pin "36") (pinfunction "PB15_36") (pintype "bidirectional"))
    )
    (net (code "66") (name "unconnected-(U1A-PC1-Pad9)") (class "Default")
      (node (ref "U1") (pin "9") (pinfunction "PC1_9") (pintype "bidirectional"))
    )
    (net (code "67") (name "unconnected-(U1A-PC4-Pad24)") (class "Default")
      (node (ref "U1") (pin "24") (pinfunction "PC4_24") (pintype "bidirectional"))
    )
    (net (code "68") (name "unconnected-(U1A-PC5-Pad25)") (class "Default")
      (node (ref "U1") (pin "25") (pinfunction "PC5_25") (pintype "bidirectional"))
    )
    (net (code "69") (name "unconnected-(U1A-PC6-Pad37)") (class "Default")
      (node (ref "U1") (pin "37") (pinfunction "PC6_37") (pintype "bidirectional"))
    )
    (net (code "70") (name "unconnected-(U1A-PC7-Pad38)") (class "Default")
      (node (ref "U1") (pin "38") (pinfunction "PC7_38") (pintype "bidirectional"))
    )
    (net (code "71") (name "unconnected-(U1A-PC13-Pad2)") (class "Default")
      (node (ref "U1") (pin "2") (pinfunction "PC13_2") (pintype "bidirectional"))
    )
    (net (code "72") (name "unconnected-(U1A-PC14-OSC32_IN(PC14)-Pad3)") (class "Default")
      (node (ref "U1") (pin "3") (pinfunction "PC14-OSC32_IN(PC14)_3") (pintype "bidirectional"))
    )
    (net (code "73") (name "unconnected-(U1A-PC15-OSC32_OUT(PC15)-Pad4)") (class "Default")
      (node (ref "U1") (pin "4") (pinfunction "PC15-OSC32_OUT(PC15)_4") (pintype "bidirectional"))
    )
    (net (code "74") (name "unconnected-(U3-*SUSPEND-Pad11)") (class "Default")
      (node (ref "U3") (pin "11") (pinfunction "*SUSPEND_11") (pintype "passive"))
    )
    (net (code "75") (name "unconnected-(U3-CTS-Pad23)") (class "Default")
      (node (ref "U3") (pin "23") (pinfunction "CTS_23") (pintype "passive"))
    )
    (net (code "76") (name "unconnected-(U3-DCD-Pad1)") (class "Default")
      (node (ref "U3") (pin "1") (pinfunction "DCD_1") (pintype "passive"))
    )
    (net (code "77") (name "unconnected-(U3-DSR-Pad27)") (class "Default")
      (node (ref "U3") (pin "27") (pinfunction "DSR_27") (pintype "passive"))
    )
    (net (code "78") (name "unconnected-(U3-DTR-Pad28)") (class "Default")
      (node (ref "U3") (pin "28") (pinfunction "DTR_28") (pintype "passive"))
    )
    (net (code "79") (name "unconnected-(U3-NC-Pad10)") (class "Default")
      (node (ref "U3") (pin "10") (pinfunction "NC_10") (pintype "passive"))
    )
    (net (code "80") (name "unconnected-(U3-NC-Pad13)") (class "Default")
      (node (ref "U3") (pin "13") (pinfunction "NC_13") (pintype "passive"))
    )
    (net (code "81") (name "unconnected-(U3-NC-Pad14)") (class "Default")
      (node (ref "U3") (pin "14") (pinfunction "NC_14") (pintype "passive"))
    )
    (net (code "82") (name "unconnected-(U3-NC-Pad15)") (class "Default")
      (node (ref "U3") (pin "15") (pinfunction "NC_15") (pintype "passive"))
    )
    (net (code "83") (name "unconnected-(U3-NC-Pad16)") (class "Default")
      (node (ref "U3") (pin "16") (pinfunction "NC_16") (pintype "passive"))
    )
    (net (code "84") (name "unconnected-(U3-NC-Pad17)") (class "Default")
      (node (ref "U3") (pin "17") (pinfunction "NC_17") (pintype "passive"))
    )
    (net (code "85") (name "unconnected-(U3-NC-Pad18)") (class "Default")
      (node (ref "U3") (pin "18") (pinfunction "NC_18") (pintype "passive"))
    )
    (net (code "86") (name "unconnected-(U3-NC-Pad19)") (class "Default")
      (node (ref "U3") (pin "19") (pinfunction "NC_19") (pintype "passive"))
    )
    (net (code "87") (name "unconnected-(U3-NC-Pad20)") (class "Default")
      (node (ref "U3") (pin "20") (pinfunction "NC_20") (pintype "passive"))
    )
    (net (code "88") (name "unconnected-(U3-NC-Pad21)") (class "Default")
      (node (ref "U3") (pin "21") (pinfunction "NC_21") (pintype "passive"))
    )
    (net (code "89") (name "unconnected-(U3-NC-Pad22)") (class "Default")
      (node (ref "U3") (pin "22") (pinfunction "NC_22") (pintype "passive"))
    )
    (net (code "90") (name "unconnected-(U3-RI-Pad2)") (class "Default")
      (node (ref "U3") (pin "2") (pinfunction "RI_2") (pintype "passive"))
    )
    (net (code "91") (name "unconnected-(U3-RTS-Pad24)") (class "Default")
      (node (ref "U3") (pin "24") (pinfunction "RTS_24") (pintype "passive"))
    )
    (net (code "92") (name "unconnected-(U3-SUSPEND-Pad12)") (class "Default")
      (node (ref "U3") (pin "12") (pinfunction "SUSPEND_12") (pintype "passive"))
    )
    (net (code "93") (name "unconnected-(U3-VDD-Pad6)") (class "Default")
      (node (ref "U3") (pin "6") (pinfunction "VDD_6") (pintype "passive"))
    )
    (net (code "94") (name "unconnected-(U4-CPEN-Pad3)") (class "Default")
      (node (ref "U4") (pin "3") (pinfunction "CPEN_3") (pintype "output+no_connect"))
    )
    (net (code "95") (name "unconnected-(U4-EXTVBUS-Pad10)") (class "Default")
      (node (ref "U4") (pin "10") (pinfunction "EXTVBUS_10") (pintype "input+no_connect"))
    )
    (net (code "96") (name "unconnected-(U4-ID-Pad5)") (class "Default")
      (node (ref "U4") (pin "5") (pinfunction "ID_5") (pintype "input+no_connect"))
    )
  )
)
